# MOSFET.net
KiCad netlist of a schematic drawn in Altium Designer
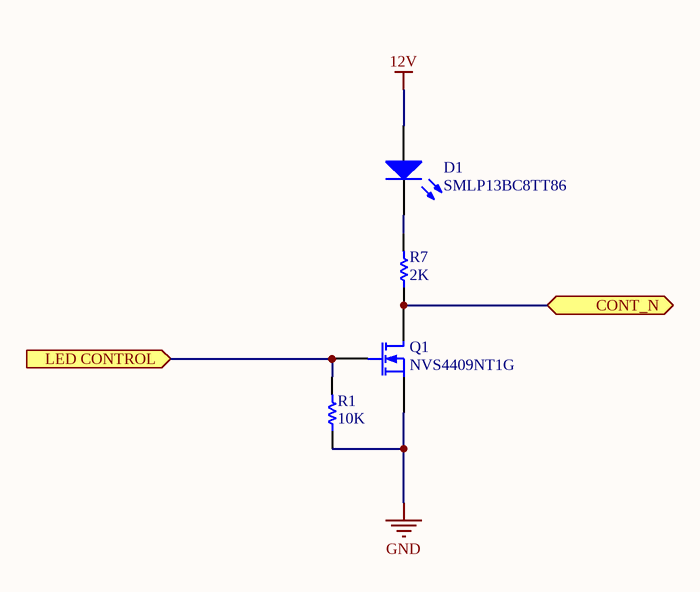
[diagram p0: MOSFET.SchDoc]

(export (version "E")
  (design (tool "Eeschema 10.0.6"))
  (components
    (comp (ref "D1")
      (value "SMLP13BC8TT86")
      (footprint "SMLP13BC8TT86")
      (description "Blue 470nm LED Indication - Discrete 2.9V 2-SMD, No Lead")
      (fields (field (name "PUBLISHER") "Altium Limited"))
      (libsource (lib "Miscellaneous Devices") (part "LED2"))
    )
    (comp (ref "Q1")
      (value "NVS4409NT1G")
      (footprint "NVS4409NT1G")
      (description "N-Channel 25V 700mA (Ta) 280mW (Tj) Surface Mount SC-70-3 (SOT323)")
      (fields (field (name "PUBLISHER") "Altium Limited"))
      (libsource (lib "Miscellaneous Devices") (part "MOSFET-N"))
    )
    (comp (ref "R1")
      (value "10K")
      (footprint "J1-0603")
      (fields (field (name "Comment") "5%") (field (name "PUBLISHER") "Altium Limited"))
      (libsource (lib "Miscellaneous Devices") (part "Res1"))
    )
    (comp (ref "R7")
      (value "2K")
      (footprint "J1-0603")
      (fields (field (name "Comment") "5%") (field (name "PUBLISHER") "Altium Limited"))
      (libsource (lib "Miscellaneous Devices") (part "Res1"))
    )
  )
  (nets
    (net (code "1") (name "/CONT_N") (class "Default")
      (node (ref "Q1") (pin "1") (pinfunction "D_1") (pintype "passive"))
      (node (ref "R7") (pin "1") (pinfunction "1_1") (pintype "passive"))
    )
    (net (code "2") (name "/LED CONTROL") (class "Default")
      (node (ref "Q1") (pin "2") (pinfunction "G_2") (pintype "passive"))
      (node (ref "R1") (pin "2") (pinfunction "2_2") (pintype "passive"))
    )
    (net (code "3") (name "12V") (class "Default")
      (node (ref "D1") (pin "1") (pinfunction "A_1") (pintype "passive"))
    )
    (net (code "4") (name "GND") (class "Default")
      (node (ref "Q1") (pin "3") (pinfunction "S_3") (pintype "passive"))
      (node (ref "R1") (pin "1") (pinfunction "1_1") (pintype "passive"))
    )
    (net (code "5") (name "Net-(D1-K)") (class "Default")
      (node (ref "D1") (pin "2") (pinfunction "K_2") (pintype "passive"))
      (node (ref "R7") (pin "2") (pinfunction "2_2") (pintype "passive"))
    )
  )
)
